# 07_i2cBridge.net
KiCad netlist of a schematic drawn in Altium Designer
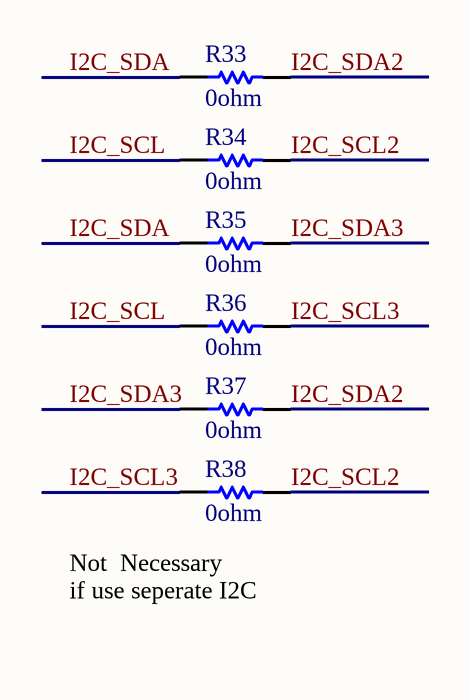
[diagram p0: 07_i2cBridge.SchDoc]

(export (version "E")
  (design (tool "Eeschema 10.0.6"))
  (components
    (comp (ref "R33")
      (value "0ohm")
      (footprint "RESC1608X55X25ML10T15")
      (description "Chip Resistor, 0 Ohm, +/- 5%, 0.1 W, -55 to 155 degC, 0603 (1608 Metric), RoHS, Tape and Reel")
      (fields (field (name "TOLERANCE") "5%") (field (name "MANUFACTURER") "Yageo"))
      (libsource (lib "Altium Content Vault") (part "RES-2"))
    )
    (comp (ref "R34")
      (value "0ohm")
      (footprint "RESC1608X55X25ML10T15")
      (description "Chip Resistor, 0 Ohm, +/- 5%, 0.1 W, -55 to 155 degC, 0603 (1608 Metric), RoHS, Tape and Reel")
      (fields (field (name "TOLERANCE") "5%") (field (name "MANUFACTURER") "Yageo"))
      (libsource (lib "Altium Content Vault") (part "RES-2"))
    )
    (comp (ref "R35")
      (value "0ohm")
      (footprint "RESC1608X55X25ML10T15")
      (description "Chip Resistor, 0 Ohm, +/- 5%, 0.1 W, -55 to 155 degC, 0603 (1608 Metric), RoHS, Tape and Reel")
      (fields (field (name "TOLERANCE") "5%") (field (name "MANUFACTURER") "Yageo"))
      (libsource (lib "Altium Content Vault") (part "RES-2"))
    )
    (comp (ref "R36")
      (value "0ohm")
      (footprint "RESC1608X55X25ML10T15")
      (description "Chip Resistor, 0 Ohm, +/- 5%, 0.1 W, -55 to 155 degC, 0603 (1608 Metric), RoHS, Tape and Reel")
      (fields (field (name "TOLERANCE") "5%") (field (name "MANUFACTURER") "Yageo"))
      (libsource (lib "Altium Content Vault") (part "RES-2"))
    )
    (comp (ref "R37")
      (value "0ohm")
      (footprint "RESC1608X55X25ML10T15")
      (description "Chip Resistor, 0 Ohm, +/- 5%, 0.1 W, -55 to 155 degC, 0603 (1608 Metric), RoHS, Tape and Reel")
      (fields (field (name "TOLERANCE") "5%") (field (name "MANUFACTURER") "Yageo"))
      (libsource (lib "Altium Content Vault") (part "RES-2"))
    )
    (comp (ref "R38")
      (value "0ohm")
      (footprint "RESC1608X55X25ML10T15")
      (description "Chip Resistor, 0 Ohm, +/- 5%, 0.1 W, -55 to 155 degC, 0603 (1608 Metric), RoHS, Tape and Reel")
      (fields (field (name "TOLERANCE") "5%") (field (name "MANUFACTURER") "Yageo"))
      (libsource (lib "Altium Content Vault") (part "RES-2"))
    )
  )
  (nets
    (net (code "1") (name "/I2C_SCL") (class "Default")
      (node (ref "R34") (pin "1") (pinfunction "1_1") (pintype "passive"))
      (node (ref "R36") (pin "1") (pinfunction "1_1") (pintype "passive"))
    )
    (net (code "2") (name "/I2C_SCL2") (class "Default")
      (node (ref "R34") (pin "2") (pinfunction "2_2") (pintype "passive"))
      (node (ref "R38") (pin "2") (pinfunction "2_2") (pintype "passive"))
    )
    (net (code "3") (name "/I2C_SCL3") (class "Default")
      (node (ref "R36") (pin "2") (pinfunction "2_2") (pintype "passive"))
      (node (ref "R38") (pin "1") (pinfunction "1_1") (pintype "passive"))
    )
    (net (code "4") (name "/I2C_SDA") (class "Default")
      (node (ref "R33") (pin "1") (pinfunction "1_1") (pintype "passive"))
      (node (ref "R35") (pin "1") (pinfunction "1_1") (pintype "passive"))
    )
    (net (code "5") (name "/I2C_SDA2") (class "Default")
      (node (ref "R33") (pin "2") (pinfunction "2_2") (pintype "passive"))
      (node (ref "R37") (pin "2") (pinfunction "2_2") (pintype "passive"))
    )
    (net (code "6") (name "/I2C_SDA3") (class "Default")
      (node (ref "R35") (pin "2") (pinfunction "2_2") (pintype "passive"))
      (node (ref "R37") (pin "1") (pinfunction "1_1") (pintype "passive"))
    )
  )
)
